# Power.net
KiCad netlist of a schematic drawn in Altium Designer
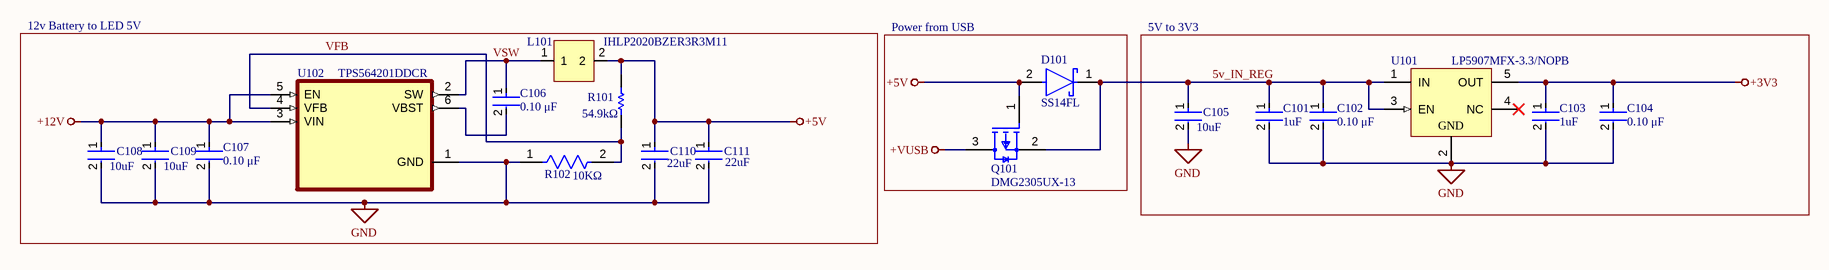
[diagram p0: Power.SchDoc]

(export (version "E")
  (design (tool "Eeschema 10.0.6"))
  (components
    (comp (ref "C101")
      (value "C0603C105K4RACAUTO")
      (footprint "FP-C0603C-CJ-MFG")
      (description "CAP CER 0603 1UF 16V X7R 10%")
      (fields
        (field (name "MANUFACTURER") "KEMET")
        (field (name "OCTOPART") "https://octopart.com/c0603c105k4racauto-kemet-91328491")
        (field (name "CAPACITANCE") "1uF")
      )
      (libsource (lib "Altium Content Vault") (part "b4654b650e69147ec39a6b967a45e02"))
    )
    (comp (ref "C102")
      (value "C0603C104K5RACAUTO")
      (footprint "FP-C0603C-CF-MFG")
      (description "CAP CER 0.1UF 50V X7R 0603")
      (fields
        (field (name "MANUFACTURER") "KEMET")
        (field (name "OCTOPART") "https://octopart.com/c0603c104k5racauto-kemet-12563741")
        (field (name "CAPACITANCE") "0.10 μF")
      )
      (libsource (lib "Altium Content Vault") (part "b4654b650e69147ec39a6b967a45e02"))
    )
    (comp (ref "C103")
      (value "C0603C105K4RACAUTO")
      (footprint "FP-C0603C-CJ-MFG")
      (description "CAP CER 0603 1UF 16V X7R 10%")
      (fields
        (field (name "MANUFACTURER") "KEMET")
        (field (name "OCTOPART") "https://octopart.com/c0603c105k4racauto-kemet-91328491")
        (field (name "CAPACITANCE") "1uF")
      )
      (libsource (lib "Altium Content Vault") (part "b4654b650e69147ec39a6b967a45e02"))
    )
    (comp (ref "C104")
      (value "C0603C104K5RACAUTO")
      (footprint "FP-C0603C-CF-MFG")
      (description "CAP CER 0.1UF 50V X7R 0603")
      (fields
        (field (name "MANUFACTURER") "KEMET")
        (field (name "OCTOPART") "https://octopart.com/c0603c104k5racauto-kemet-12563741")
        (field (name "CAPACITANCE") "0.10 μF")
      )
      (libsource (lib "Altium Content Vault") (part "b4654b650e69147ec39a6b967a45e02"))
    )
    (comp (ref "C105")
      (value "GRM31CR71E106KA12K")
      (footprint "FP-GRM31C-0_2-e0_3_0_8-MFG")
      (description "Chip Multilayer Ceramic Capacitors for General Purpose, 1206, 10uF, X7R, 15%, 10%, 25V")
      (fields
        (field (name "CAPACITANCE") "10uF")
        (field (name "TOLERANCE") "10%")
        (field (name "VOLTAGE") "25V")
      )
      (libsource (lib "Altium Content Vault") (part "02cd4be3c70576c341d710602a673aa"))
    )
    (comp (ref "C106")
      (value "C0603C104K5RACAUTO")
      (footprint "FP-C0603C-CF-MFG")
      (description "CAP CER 0.1UF 50V X7R 0603")
      (fields
        (field (name "MANUFACTURER") "KEMET")
        (field (name "OCTOPART") "https://octopart.com/c0603c104k5racauto-kemet-12563741")
        (field (name "CAPACITANCE") "0.10 μF")
      )
      (libsource (lib "Altium Content Vault") (part "b4654b650e69147ec39a6b967a45e02"))
    )
    (comp (ref "C107")
      (value "C0603C104K5RACAUTO")
      (footprint "FP-C0603C-CF-MFG")
      (description "CAP CER 0.1UF 50V X7R 0603")
      (fields
        (field (name "MANUFACTURER") "KEMET")
        (field (name "OCTOPART") "https://octopart.com/c0603c104k5racauto-kemet-12563741")
        (field (name "CAPACITANCE") "0.10 μF")
      )
      (libsource (lib "Altium Content Vault") (part "b4654b650e69147ec39a6b967a45e02"))
    )
    (comp (ref "C108")
      (value "GRM31CR71E106KA12K")
      (footprint "FP-GRM31C-0_2-e0_3_0_8-MFG")
      (description "Chip Multilayer Ceramic Capacitors for General Purpose, 1206, 10uF, X7R, 15%, 10%, 25V")
      (fields
        (field (name "CAPACITANCE") "10uF")
        (field (name "TOLERANCE") "10%")
        (field (name "VOLTAGE") "25V")
      )
      (libsource (lib "Altium Content Vault") (part "02cd4be3c70576c341d710602a673aa"))
    )
    (comp (ref "C109")
      (value "GRM31CR71E106KA12K")
      (footprint "FP-GRM31C-0_2-e0_3_0_8-MFG")
      (description "Chip Multilayer Ceramic Capacitors for General Purpose, 1206, 10uF, X7R, 15%, 10%, 25V")
      (fields
        (field (name "CAPACITANCE") "10uF")
        (field (name "TOLERANCE") "10%")
        (field (name "VOLTAGE") "25V")
      )
      (libsource (lib "Altium Content Vault") (part "02cd4be3c70576c341d710602a673aa"))
    )
    (comp (ref "C110")
      (value "22uF")
      (footprint "FP-CL31H-0_2-MFG")
      (description "CAP CER 22UF 25V X5R 1206")
      (fields
        (field (name "OCTOPART") "https://octopart.com/cl31a226kahnnne-samsung-19832795")
        (field (name "TOLERANCE") "10%")
      )
      (libsource (lib "Altium Content Vault") (part "11868f565c42a9108669ba33697ecf6"))
    )
    (comp (ref "C111")
      (value "22uF")
      (footprint "FP-CL31H-0_2-MFG")
      (description "CAP CER 22UF 25V X5R 1206")
      (fields
        (field (name "OCTOPART") "https://octopart.com/cl31a226kahnnne-samsung-19832795")
        (field (name "TOLERANCE") "10%")
      )
      (libsource (lib "Altium Content Vault") (part "11868f565c42a9108669ba33697ecf6"))
    )
    (comp (ref "D101")
      (value "SS14FL")
      (footprint "FP-425AD-MFG")
      (description "DIODE SCHOTTKY 40V 1A SOD123F")
      (fields
        (field (name "MANUFACTURER") "ON Semiconductor")
        (field (name "OCTOPART") "https://octopart.com/ss14fl-on+semiconductor-84331601")
      )
      (libsource (lib "Altium Content Vault") (part "c1678fac7984e62e0809fbf79c06691"))
    )
    (comp (ref "L101")
      (value "IHLP2020BZER3R3M11")
      (footprint "IHLP2020BZER3R3M11")
      (libsource (lib "Timing Display") (part "IHLP2020BZER3R3M11"))
    )
    (comp (ref "Q101")
      (value "DMG2305UX-13")
      (footprint "FP-SOT23-MFG")
      (description "MOSFET P-CH 20V 4.2A SOT23")
      (fields
        (field (name "MANUFACTURER") "Diodes Inc.")
        (field (name "OCTOPART") "https://octopart.com/dmg2305ux-13-diodes+inc.-29925594")
      )
      (libsource (lib "Altium Content Vault") (part "b298ed0aef6ca29edb293456b19cad3"))
    )
    (comp (ref "R101")
      (value "54.9kΩ")
      (footprint "RESC1608X55X30LL15T15")
      (fields (field (name "MANUFACTURER") "Panasonic") (field (name "PART NUMBER") "ERJ-3EKF5492V"))
      (libsource (lib "Altium Content Vault") (part "RES"))
    )
    (comp (ref "R102")
      (value "AC0603FR-0710KL")
      (footprint "FP-AC0603-MFG")
      (description "RES SMD 10K OHM 1% 1/10W 0603")
      (fields
        (field (name "MANUFACTURER") "Yageo")
        (field (name "TOLERANCE") "0.01")
        (field (name "RESISTANCE") "10KΩ")
      )
      (libsource (lib "Altium Content Vault") (part "1029c3af85768c4190bb7ad29bc67b5"))
    )
    (comp (ref "U101")
      (value "LP5907MFX-3.3/NOPB")
      (footprint "DBV0005A_N")
      (description "None")
      (libsource (lib "Altium Content Vault") (part "TI-LP5907-SOT-23-5"))
    )
    (comp (ref "U102")
      (value "TPS564201DDCR")
      (footprint "TPS564201DDCR:SOT95P280X110-6N")
      (fields (field (name "MF") "{'manufacturer': u'Texas Instruments'}"))
      (libsource (lib "*") (part "TPS564201DDCR"))
    )
  )
  (nets
    (net (code "1") (name "+3V3") (class "Default")
      (node (ref "C103") (pin "1") (pinfunction "1_1") (pintype "passive"))
      (node (ref "C104") (pin "1") (pinfunction "1_1") (pintype "passive"))
      (node (ref "U101") (pin "5") (pinfunction "OUT_5") (pintype "power_in"))
    )
    (net (code "2") (name "+5V") (class "Default")
      (node (ref "C110") (pin "1") (pinfunction "1_1") (pintype "passive"))
      (node (ref "C111") (pin "1") (pinfunction "1_1") (pintype "passive"))
      (node (ref "D101") (pin "2") (pinfunction "A_2") (pintype "passive"))
      (node (ref "L101") (pin "2") (pinfunction "2_2") (pintype "passive"))
      (node (ref "Q101") (pin "1") (pinfunction "G_1") (pintype "passive"))
      (node (ref "R101") (pin "2") (pinfunction "2_2") (pintype "passive"))
    )
    (net (code "3") (name "+12V") (class "Default")
      (node (ref "C107") (pin "1") (pinfunction "1_1") (pintype "passive"))
      (node (ref "C108") (pin "1") (pinfunction "1_1") (pintype "passive"))
      (node (ref "C109") (pin "1") (pinfunction "1_1") (pintype "passive"))
      (node (ref "U102") (pin "3") (pinfunction "VIN_3") (pintype "input"))
      (node (ref "U102") (pin "5") (pinfunction "EN_5") (pintype "input"))
    )
    (net (code "4") (name "+VUSB") (class "Default")
      (node (ref "Q101") (pin "3") (pinfunction "D_3") (pintype "passive"))
    )
    (net (code "5") (name "/5v_IN_REG") (class "Default")
      (node (ref "C101") (pin "1") (pinfunction "1_1") (pintype "passive"))
      (node (ref "C102") (pin "1") (pinfunction "1_1") (pintype "passive"))
      (node (ref "C105") (pin "1") (pinfunction "1_1") (pintype "passive"))
      (node (ref "D101") (pin "1") (pinfunction "C_1") (pintype "passive"))
      (node (ref "Q101") (pin "2") (pinfunction "S_2") (pintype "passive"))
      (node (ref "U101") (pin "1") (pinfunction "IN_1") (pintype "power_in"))
      (node (ref "U101") (pin "3") (pinfunction "EN_3") (pintype "input"))
    )
    (net (code "6") (name "/VFB") (class "Default")
      (node (ref "R101") (pin "1") (pinfunction "1_1") (pintype "passive"))
      (node (ref "R102") (pin "2") (pinfunction "2_2") (pintype "passive"))
      (node (ref "U102") (pin "4") (pinfunction "VFB_4") (pintype "input"))
    )
    (net (code "7") (name "/VSW") (class "Default")
      (node (ref "C106") (pin "1") (pinfunction "1_1") (pintype "passive"))
      (node (ref "L101") (pin "1") (pinfunction "1_1") (pintype "passive"))
      (node (ref "U102") (pin "2") (pinfunction "SW_2") (pintype "output"))
    )
    (net (code "8") (name "GND") (class "Default")
      (node (ref "C101") (pin "2") (pinfunction "2_2") (pintype "passive"))
      (node (ref "C102") (pin "2") (pinfunction "2_2") (pintype "passive"))
      (node (ref "C103") (pin "2") (pinfunction "2_2") (pintype "passive"))
      (node (ref "C104") (pin "2") (pinfunction "2_2") (pintype "passive"))
      (node (ref "C105") (pin "2") (pinfunction "2_2") (pintype "passive"))
      (node (ref "C107") (pin "2") (pinfunction "2_2") (pintype "passive"))
      (node (ref "C108") (pin "2") (pinfunction "2_2") (pintype "passive"))
      (node (ref "C109") (pin "2") (pinfunction "2_2") (pintype "passive"))
      (node (ref "C110") (pin "2") (pinfunction "2_2") (pintype "passive"))
      (node (ref "C111") (pin "2") (pinfunction "2_2") (pintype "passive"))
      (node (ref "R102") (pin "1") (pinfunction "1_1") (pintype "passive"))
      (node (ref "U101") (pin "2") (pinfunction "GND_2") (pintype "power_in"))
      (node (ref "U102") (pin "1") (pinfunction "GND_1") (pintype "power_in"))
    )
    (net (code "9") (name "Net-(U102-VBST)") (class "Default")
      (node (ref "C106") (pin "2") (pinfunction "2_2") (pintype "passive"))
      (node (ref "U102") (pin "6") (pinfunction "VBST_6") (pintype "output"))
    )
    (net (code "10") (name "unconnected-(U101-NC-Pad4)") (class "Default")
      (node (ref "U101") (pin "4") (pinfunction "NC_4") (pintype "passive+no_connect"))
    )
  )
)
